# fc_shield.net
KiCad netlist of a schematic drawn in EAGLE
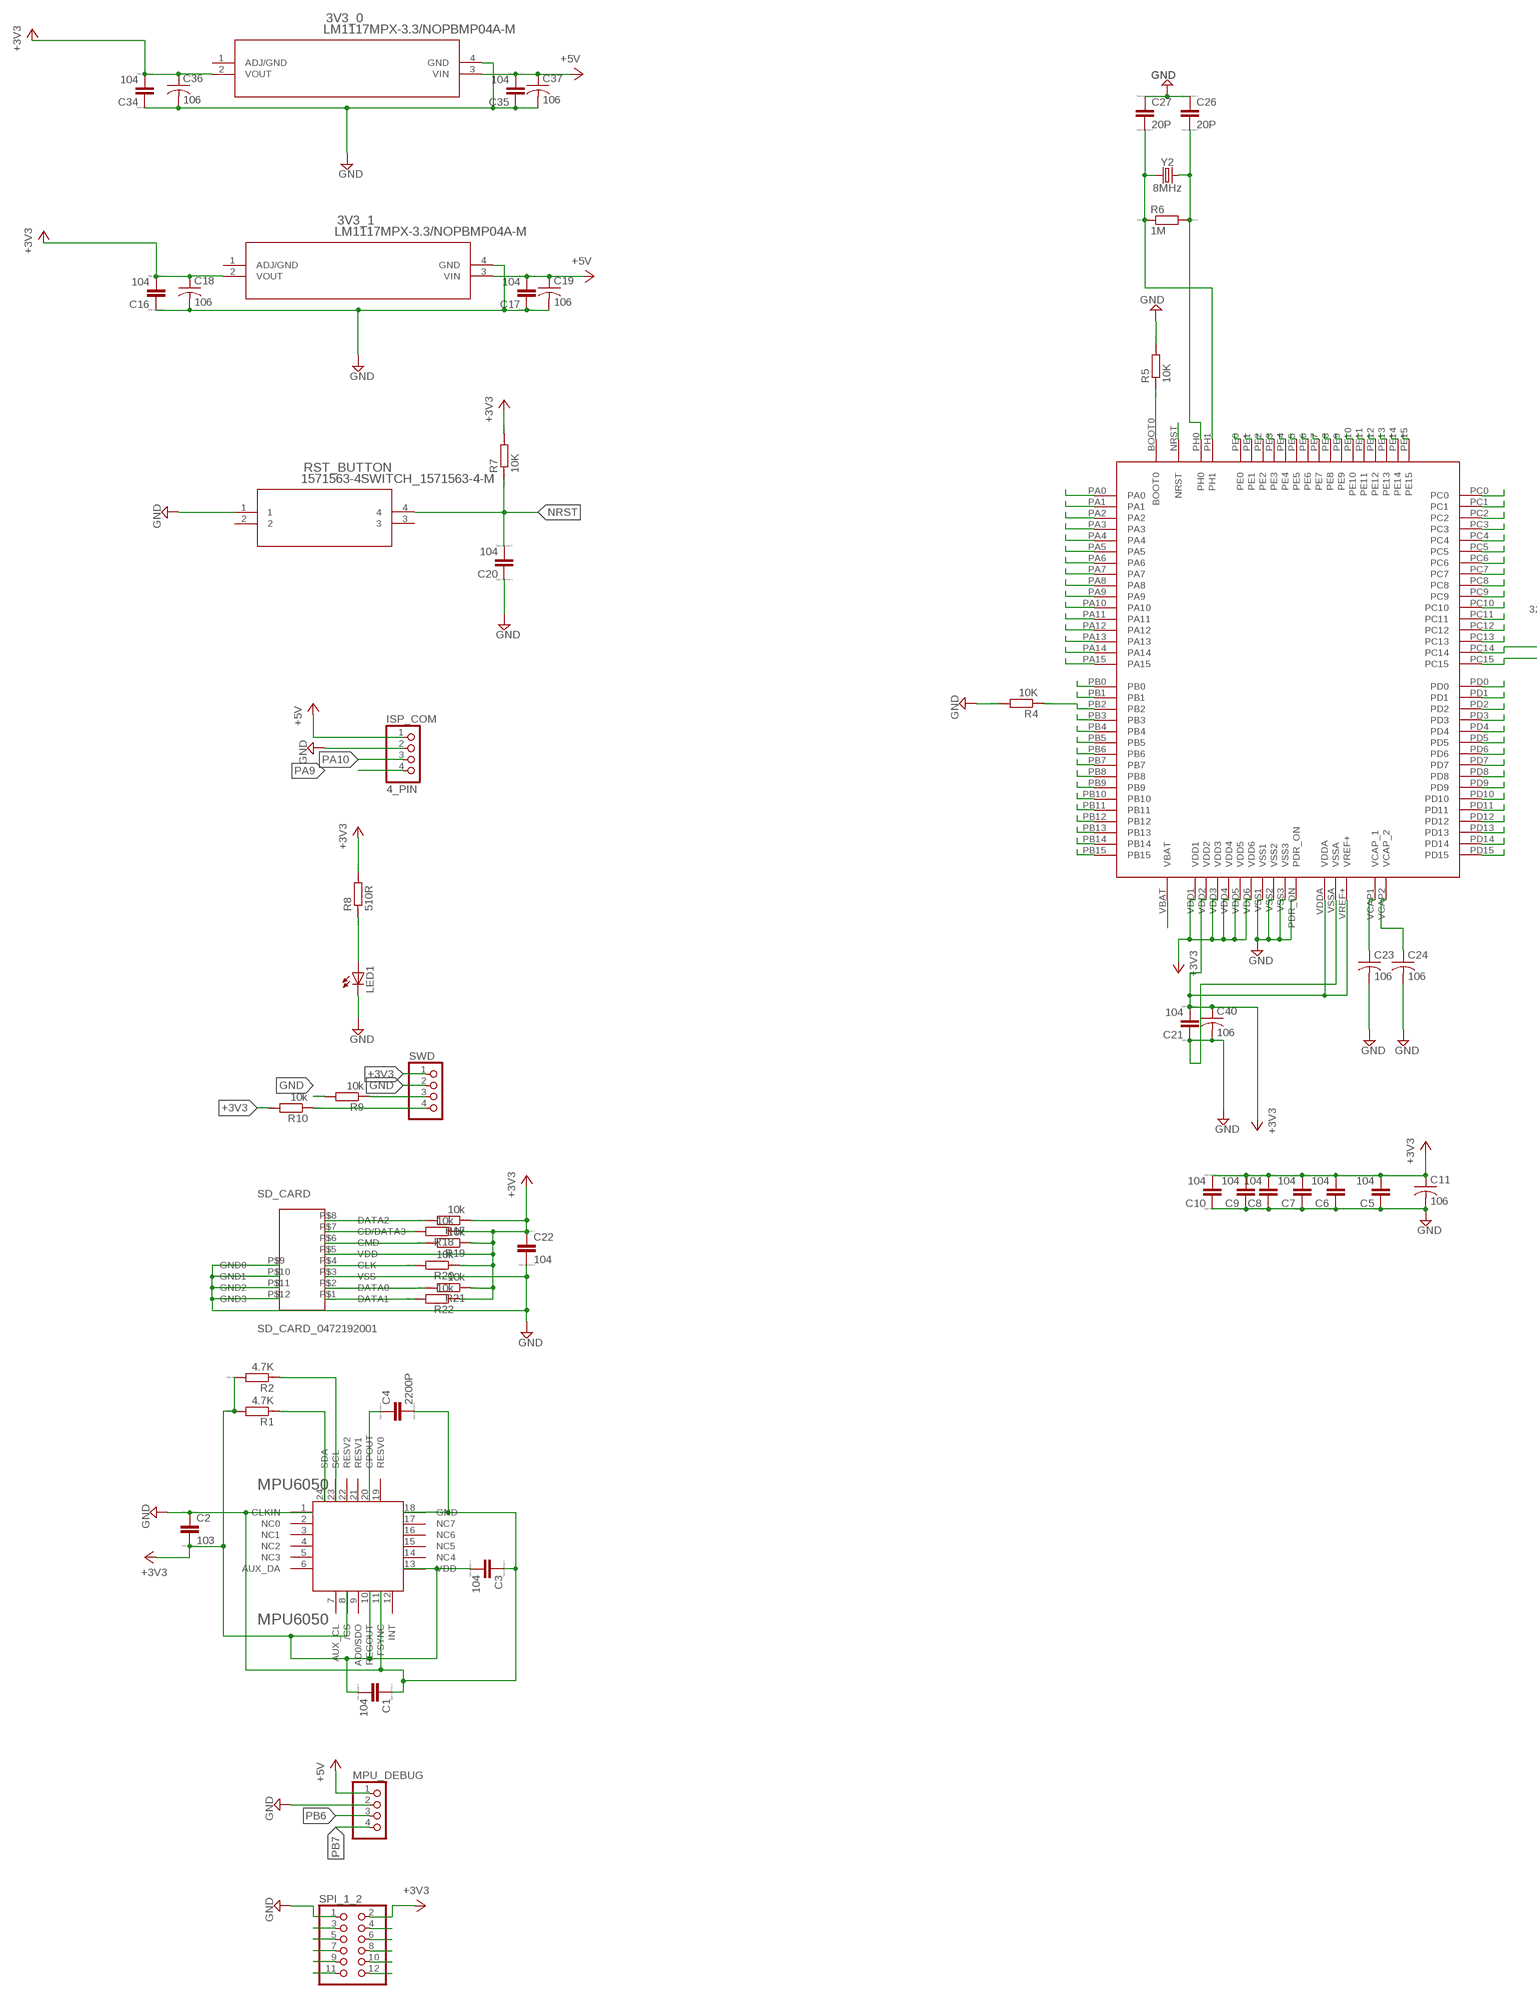
[diagram p0: schematic, sheet 1, part 1 of 2]
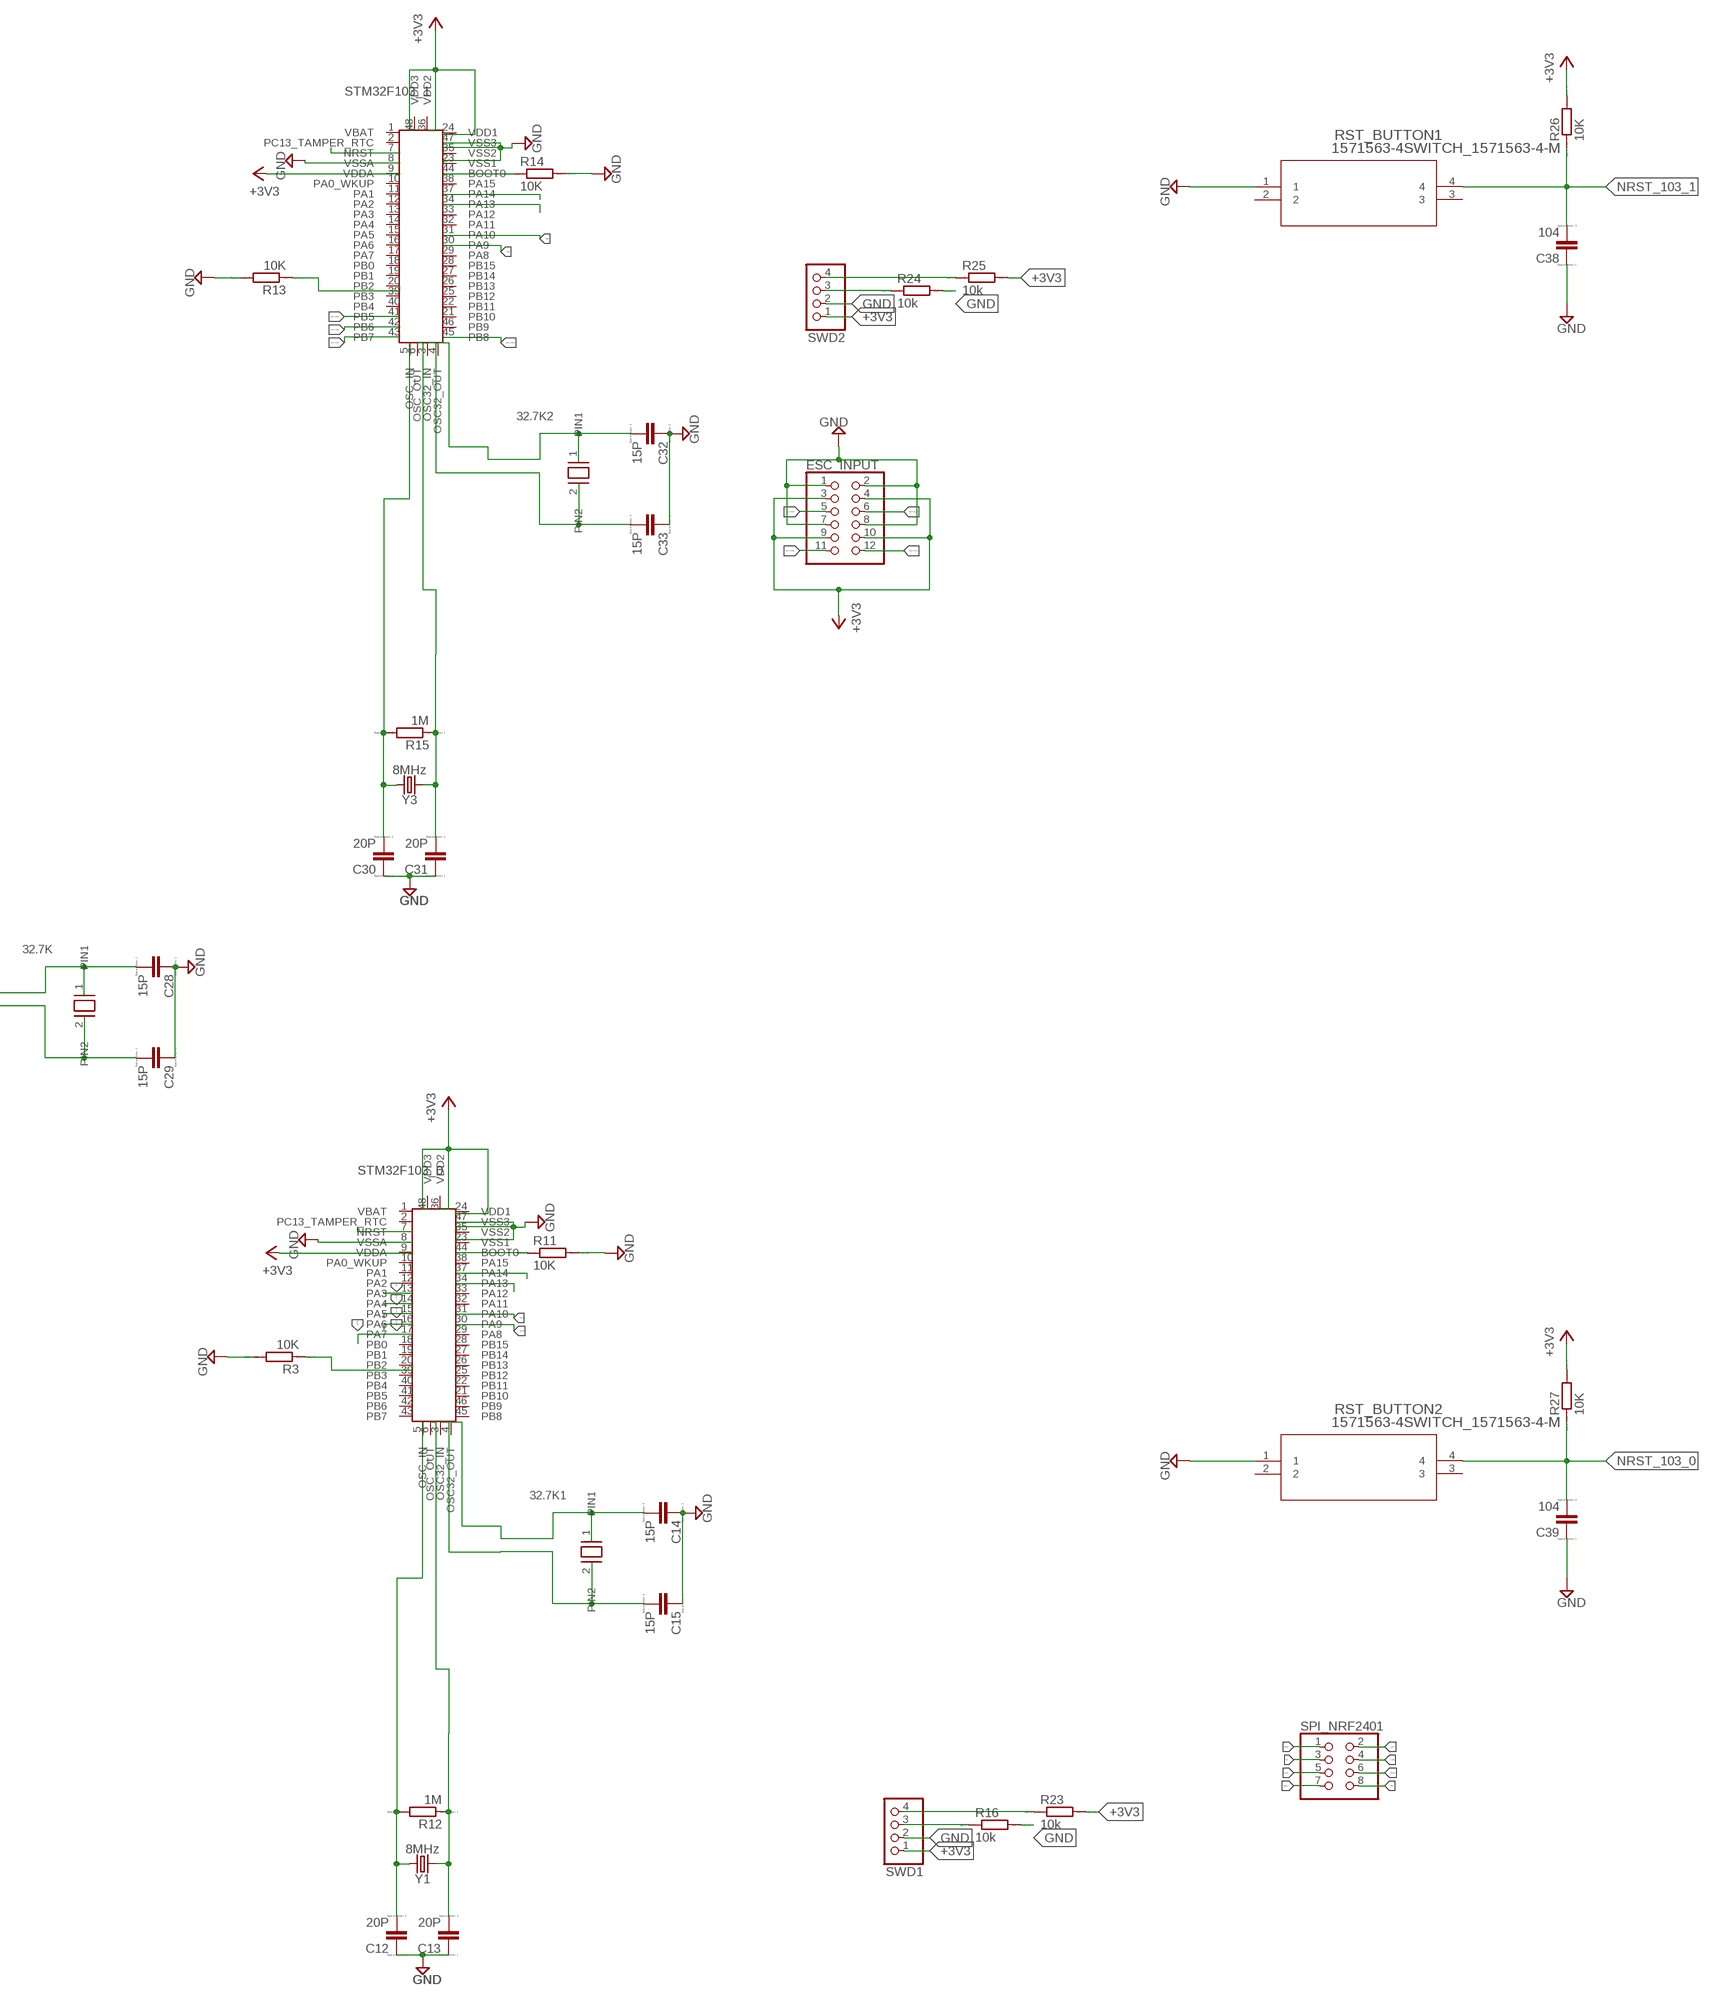
[diagram p1: schematic, sheet 1, part 2 of 2]

(export (version "E")
  (design (tool "Eeschema 10.0.6"))
  (components
    (comp (ref "3V3_0")
      (value "LM1117MPX-3.3/NOPBMP04A-M")
      (footprint "eagle-import:MP04A-M")
      (fields (field (name "MANUFACTURER_PART_NUMBER") "LM1117MPX3.3NOPB"))
      (libsource (lib "eagle-import") (part "LM1117MPX-3.3/NOPBMP04A-M"))
    )
    (comp (ref "3V3_1")
      (value "LM1117MPX-3.3/NOPBMP04A-M")
      (footprint "eagle-import:MP04A-M")
      (fields (field (name "MANUFACTURER_PART_NUMBER") "LM1117MPX3.3NOPB"))
      (libsource (lib "eagle-import") (part "LM1117MPX-3.3/NOPBMP04A-M"))
    )
    (comp (ref "32.7K")
      (value "CM315D")
      (footprint "eagle-import:CM315D_32.7K")
      (libsource (lib "eagle-import") (part "CM315D"))
    )
    (comp (ref "32.7K1")
      (value "CM315D")
      (footprint "eagle-import:CM315D_32.7K")
      (libsource (lib "eagle-import") (part "CM315D"))
    )
    (comp (ref "32.7K2")
      (value "CM315D")
      (footprint "eagle-import:CM315D_32.7K")
      (libsource (lib "eagle-import") (part "CM315D"))
    )
    (comp (ref "C1")
      (value "104")
      (footprint "eagle-import:C0603")
      (libsource (lib "eagle-import") (part "CC0603"))
    )
    (comp (ref "C2")
      (value "103")
      (footprint "eagle-import:C0603")
      (libsource (lib "eagle-import") (part "CC0603"))
    )
    (comp (ref "C3")
      (value "104")
      (footprint "eagle-import:C0603")
      (libsource (lib "eagle-import") (part "CC0603"))
    )
    (comp (ref "C4")
      (value "2200P")
      (footprint "eagle-import:C0603")
      (libsource (lib "eagle-import") (part "CC0603"))
    )
    (comp (ref "C5")
      (value "104")
      (footprint "eagle-import:C0603")
      (libsource (lib "eagle-import") (part "CC0603"))
    )
    (comp (ref "C6")
      (value "104")
      (footprint "eagle-import:C0603")
      (libsource (lib "eagle-import") (part "CC0603"))
    )
    (comp (ref "C7")
      (value "104")
      (footprint "eagle-import:C0603")
      (libsource (lib "eagle-import") (part "CC0603"))
    )
    (comp (ref "C8")
      (value "104")
      (footprint "eagle-import:C0603")
      (libsource (lib "eagle-import") (part "CC0603"))
    )
    (comp (ref "C9")
      (value "104")
      (footprint "eagle-import:C0603")
      (libsource (lib "eagle-import") (part "CC0603"))
    )
    (comp (ref "C10")
      (value "104")
      (footprint "eagle-import:C0603")
      (libsource (lib "eagle-import") (part "CC0603"))
    )
    (comp (ref "C11")
      (value "106")
      (footprint "eagle-import:C0805")
      (libsource (lib "eagle-import") (part "C-USC0805"))
    )
    (comp (ref "C12")
      (value "20P")
      (footprint "eagle-import:C0603")
      (libsource (lib "eagle-import") (part "CC0603"))
    )
    (comp (ref "C13")
      (value "20P")
      (footprint "eagle-import:C0603")
      (libsource (lib "eagle-import") (part "CC0603"))
    )
    (comp (ref "C14")
      (value "15P")
      (footprint "eagle-import:C0603")
      (libsource (lib "eagle-import") (part "CC0603"))
    )
    (comp (ref "C15")
      (value "15P")
      (footprint "eagle-import:C0603")
      (libsource (lib "eagle-import") (part "CC0603"))
    )
    (comp (ref "C16")
      (value "104")
      (footprint "eagle-import:C0603")
      (libsource (lib "eagle-import") (part "CC0603"))
    )
    (comp (ref "C17")
      (value "104")
      (footprint "eagle-import:C0603")
      (libsource (lib "eagle-import") (part "CC0603"))
    )
    (comp (ref "C18")
      (value "106")
      (footprint "eagle-import:C0805")
      (libsource (lib "eagle-import") (part "C-USC0805"))
    )
    (comp (ref "C19")
      (value "106")
      (footprint "eagle-import:C0805")
      (libsource (lib "eagle-import") (part "C-USC0805"))
    )
    (comp (ref "C20")
      (value "104")
      (footprint "eagle-import:C0603")
      (libsource (lib "eagle-import") (part "CC0603"))
    )
    (comp (ref "C21")
      (value "104")
      (footprint "eagle-import:C0603")
      (libsource (lib "eagle-import") (part "CC0603"))
    )
    (comp (ref "C22")
      (value "104")
      (footprint "eagle-import:C0603")
      (libsource (lib "eagle-import") (part "CC0603"))
    )
    (comp (ref "C23")
      (value "106")
      (footprint "eagle-import:C0805")
      (libsource (lib "eagle-import") (part "C-USC0805"))
    )
    (comp (ref "C24")
      (value "106")
      (footprint "eagle-import:C0805")
      (libsource (lib "eagle-import") (part "C-USC0805"))
    )
    (comp (ref "C26")
      (value "20P")
      (footprint "eagle-import:C0603")
      (libsource (lib "eagle-import") (part "CC0603"))
    )
    (comp (ref "C27")
      (value "20P")
      (footprint "eagle-import:C0603")
      (libsource (lib "eagle-import") (part "CC0603"))
    )
    (comp (ref "C28")
      (value "15P")
      (footprint "eagle-import:C0603")
      (libsource (lib "eagle-import") (part "CC0603"))
    )
    (comp (ref "C29")
      (value "15P")
      (footprint "eagle-import:C0603")
      (libsource (lib "eagle-import") (part "CC0603"))
    )
    (comp (ref "C30")
      (value "20P")
      (footprint "eagle-import:C0603")
      (libsource (lib "eagle-import") (part "CC0603"))
    )
    (comp (ref "C31")
      (value "20P")
      (footprint "eagle-import:C0603")
      (libsource (lib "eagle-import") (part "CC0603"))
    )
    (comp (ref "C32")
      (value "15P")
      (footprint "eagle-import:C0603")
      (libsource (lib "eagle-import") (part "CC0603"))
    )
    (comp (ref "C33")
      (value "15P")
      (footprint "eagle-import:C0603")
      (libsource (lib "eagle-import") (part "CC0603"))
    )
    (comp (ref "C34")
      (value "104")
      (footprint "eagle-import:C0603")
      (libsource (lib "eagle-import") (part "CC0603"))
    )
    (comp (ref "C35")
      (value "104")
      (footprint "eagle-import:C0603")
      (libsource (lib "eagle-import") (part "CC0603"))
    )
    (comp (ref "C36")
      (value "106")
      (footprint "eagle-import:C0805")
      (libsource (lib "eagle-import") (part "C-USC0805"))
    )
    (comp (ref "C37")
      (value "106")
      (footprint "eagle-import:C0805")
      (libsource (lib "eagle-import") (part "C-USC0805"))
    )
    (comp (ref "C38")
      (value "104")
      (footprint "eagle-import:C0603")
      (libsource (lib "eagle-import") (part "CC0603"))
    )
    (comp (ref "C39")
      (value "104")
      (footprint "eagle-import:C0603")
      (libsource (lib "eagle-import") (part "CC0603"))
    )
    (comp (ref "C40")
      (value "106")
      (footprint "eagle-import:C0805")
      (libsource (lib "eagle-import") (part "C-USC0805"))
    )
    (comp (ref "ESC_INPUT")
      (value "PINHD-2X6/90")
      (footprint "eagle-import:2X06_90")
      (libsource (lib "eagle-import") (part "PINHD-2X6/90"))
    )
    (comp (ref "ISP_COM")
      (value "4_PIN")
      (footprint "eagle-import:1X04")
      (libsource (lib "eagle-import") (part "PINHD-1X4"))
    )
    (comp (ref "LED1")
      (value "LEDCHIPLED_0805")
      (footprint "eagle-import:CHIPLED_0805")
      (libsource (lib "eagle-import") (part "LEDCHIPLED_0805"))
    )
    (comp (ref "MPU6050")
      (value "MPU6050")
      (footprint "eagle-import:MPU6050")
      (libsource (lib "eagle-import") (part "MPU6050"))
    )
    (comp (ref "MPU_DEBUG")
      (value "PINHD-1X4")
      (footprint "eagle-import:1X04")
      (libsource (lib "eagle-import") (part "PINHD-1X4"))
    )
    (comp (ref "R1")
      (value "4.7K")
      (footprint "eagle-import:R0603")
      (libsource (lib "eagle-import") (part "RR0603"))
    )
    (comp (ref "R2")
      (value "4.7K")
      (footprint "eagle-import:R0603")
      (libsource (lib "eagle-import") (part "RR0603"))
    )
    (comp (ref "R3")
      (value "10K")
      (footprint "eagle-import:R0603")
      (libsource (lib "eagle-import") (part "RR0603"))
    )
    (comp (ref "R4")
      (value "10K")
      (footprint "eagle-import:R0603")
      (libsource (lib "eagle-import") (part "RR0603"))
    )
    (comp (ref "R5")
      (value "10K")
      (footprint "eagle-import:R0603")
      (libsource (lib "eagle-import") (part "RR0603"))
    )
    (comp (ref "R6")
      (value "1M")
      (footprint "eagle-import:R0603")
      (libsource (lib "eagle-import") (part "RR0603"))
    )
    (comp (ref "R7")
      (value "10K")
      (footprint "eagle-import:R0603")
      (libsource (lib "eagle-import") (part "RR0603"))
    )
    (comp (ref "R8")
      (value "510R")
      (footprint "eagle-import:R0603")
      (libsource (lib "eagle-import") (part "RR0603"))
    )
    (comp (ref "R9")
      (value "10k")
      (footprint "eagle-import:R0603")
      (libsource (lib "eagle-import") (part "RR0603"))
    )
    (comp (ref "R10")
      (value "10k")
      (footprint "eagle-import:R0603")
      (libsource (lib "eagle-import") (part "RR0603"))
    )
    (comp (ref "R11")
      (value "10K")
      (footprint "eagle-import:R0603")
      (libsource (lib "eagle-import") (part "RR0603"))
    )
    (comp (ref "R12")
      (value "1M")
      (footprint "eagle-import:R0603")
      (libsource (lib "eagle-import") (part "RR0603"))
    )
    (comp (ref "R13")
      (value "10K")
      (footprint "eagle-import:R0603")
      (libsource (lib "eagle-import") (part "RR0603"))
    )
    (comp (ref "R14")
      (value "10K")
      (footprint "eagle-import:R0603")
      (libsource (lib "eagle-import") (part "RR0603"))
    )
    (comp (ref "R15")
      (value "1M")
      (footprint "eagle-import:R0603")
      (libsource (lib "eagle-import") (part "RR0603"))
    )
    (comp (ref "R16")
      (value "10k")
      (footprint "eagle-import:R0603")
      (libsource (lib "eagle-import") (part "RR0603"))
    )
    (comp (ref "R17")
      (value "10k")
      (footprint "eagle-import:R0603")
      (libsource (lib "eagle-import") (part "RR0603"))
    )
    (comp (ref "R18")
      (value "10k")
      (footprint "eagle-import:R0603")
      (libsource (lib "eagle-import") (part "RR0603"))
    )
    (comp (ref "R19")
      (value "10k")
      (footprint "eagle-import:R0603")
      (libsource (lib "eagle-import") (part "RR0603"))
    )
    (comp (ref "R20")
      (value "10k")
      (footprint "eagle-import:R0603")
      (libsource (lib "eagle-import") (part "RR0603"))
    )
    (comp (ref "R21")
      (value "10k")
      (footprint "eagle-import:R0603")
      (libsource (lib "eagle-import") (part "RR0603"))
    )
    (comp (ref "R22")
      (value "10k")
      (footprint "eagle-import:R0603")
      (libsource (lib "eagle-import") (part "RR0603"))
    )
    (comp (ref "R23")
      (value "10k")
      (footprint "eagle-import:R0603")
      (libsource (lib "eagle-import") (part "RR0603"))
    )
    (comp (ref "R24")
      (value "10k")
      (footprint "eagle-import:R0603")
      (libsource (lib "eagle-import") (part "RR0603"))
    )
    (comp (ref "R25")
      (value "10k")
      (footprint "eagle-import:R0603")
      (libsource (lib "eagle-import") (part "RR0603"))
    )
    (comp (ref "R26")
      (value "10K")
      (footprint "eagle-import:R0603")
      (libsource (lib "eagle-import") (part "RR0603"))
    )
    (comp (ref "R27")
      (value "10K")
      (footprint "eagle-import:R0603")
      (libsource (lib "eagle-import") (part "RR0603"))
    )
    (comp (ref "RST_BUTTON")
      (value "1571563-4SWITCH_1571563-4-M")
      (footprint "eagle-import:SWITCH_1571563-4-M")
      (fields (field (name "MANUFACTURER_PART_NUMBER") "15715634"))
      (libsource (lib "eagle-import") (part "1571563-4SWITCH_1571563-4-M"))
    )
    (comp (ref "RST_BUTTON1")
      (value "1571563-4SWITCH_1571563-4-M")
      (footprint "eagle-import:SWITCH_1571563-4-M")
      (fields (field (name "MANUFACTURER_PART_NUMBER") "15715634"))
      (libsource (lib "eagle-import") (part "1571563-4SWITCH_1571563-4-M"))
    )
    (comp (ref "RST_BUTTON2")
      (value "1571563-4SWITCH_1571563-4-M")
      (footprint "eagle-import:SWITCH_1571563-4-M")
      (fields (field (name "MANUFACTURER_PART_NUMBER") "15715634"))
      (libsource (lib "eagle-import") (part "1571563-4SWITCH_1571563-4-M"))
    )
    (comp (ref "SD_CARD")
      (value "SD_CARD_0472192001")
      (footprint "eagle-import:0472192001")
      (libsource (lib "eagle-import") (part "SD_CARD_0472192001"))
    )
    (comp (ref "SPI_1_2")
      (value "PINHD-2X6/90")
      (footprint "eagle-import:2X06_90")
      (libsource (lib "eagle-import") (part "PINHD-2X6/90"))
    )
    (comp (ref "SPI_NRF2401")
      (value "PINHD-2X4")
      (footprint "eagle-import:2X04")
      (libsource (lib "eagle-import") (part "PINHD-2X4"))
    )
    (comp (ref "STM32F103_0")
      (value "STM32F103C8T6")
      (footprint "eagle-import:STM32103C8T6_LQFP48")
      (libsource (lib "eagle-import") (part "STM32F103C8T6"))
    )
    (comp (ref "STM32F103_1")
      (value "STM32F103C8T6")
      (footprint "eagle-import:STM32103C8T6_LQFP48")
      (libsource (lib "eagle-import") (part "STM32F103C8T6"))
    )
    (comp (ref "SWD")
      (value "PINHD-1X4")
      (footprint "eagle-import:1X04")
      (libsource (lib "eagle-import") (part "PINHD-1X4"))
    )
    (comp (ref "SWD1")
      (value "PINHD-1X4")
      (footprint "eagle-import:1X04")
      (libsource (lib "eagle-import") (part "PINHD-1X4"))
    )
    (comp (ref "SWD2")
      (value "PINHD-1X4")
      (footprint "eagle-import:1X04")
      (libsource (lib "eagle-import") (part "PINHD-1X4"))
    )
    (comp (ref "U$1")
      (value "STM32F4V_100PIN_GENERIC")
      (footprint "eagle-import:LQFP100")
      (libsource (lib "eagle-import") (part "STM32F4V_100PIN_GENERIC"))
    )
    (comp (ref "Y1")
      (value "8MHz")
      (footprint "eagle-import:HC49UP")
      (libsource (lib "eagle-import") (part "CRYSTAL-8MHZSMD-HC49UP"))
    )
    (comp (ref "Y2")
      (value "8MHz")
      (footprint "eagle-import:HC49UP")
      (libsource (lib "eagle-import") (part "CRYSTAL-8MHZSMD-HC49UP"))
    )
    (comp (ref "Y3")
      (value "8MHz")
      (footprint "eagle-import:HC49UP")
      (libsource (lib "eagle-import") (part "CRYSTAL-8MHZSMD-HC49UP"))
    )
  )
  (nets
    (net (code "1") (name "+3V3") (class "Default")
      (node (ref "3V3_0") (pin "2") (pinfunction "VOUT_2") (pintype "passive"))
      (node (ref "3V3_1") (pin "2") (pinfunction "VOUT_2") (pintype "passive"))
      (node (ref "C1") (pin "2") (pinfunction "2_2") (pintype "passive"))
      (node (ref "C10") (pin "2") (pinfunction "2_2") (pintype "passive"))
      (node (ref "C11") (pin "1") (pinfunction "1_1") (pintype "passive"))
      (node (ref "C16") (pin "2") (pinfunction "2_2") (pintype "passive"))
      (node (ref "C18") (pin "1") (pinfunction "1_1") (pintype "passive"))
      (node (ref "C2") (pin "2") (pinfunction "2_2") (pintype "passive"))
      (node (ref "C21") (pin "2") (pinfunction "2_2") (pintype "passive"))
      (node (ref "C22") (pin "1") (pinfunction "1_1") (pintype "passive"))
      (node (ref "C3") (pin "2") (pinfunction "2_2") (pintype "passive"))
      (node (ref "C34") (pin "2") (pinfunction "2_2") (pintype "passive"))
      (node (ref "C36") (pin "1") (pinfunction "1_1") (pintype "passive"))
      (node (ref "C40") (pin "1") (pinfunction "1_1") (pintype "passive"))
      (node (ref "C5") (pin "2") (pinfunction "2_2") (pintype "passive"))
      (node (ref "C6") (pin "2") (pinfunction "2_2") (pintype "passive"))
      (node (ref "C7") (pin "2") (pinfunction "2_2") (pintype "passive"))
      (node (ref "C8") (pin "2") (pinfunction "2_2") (pintype "passive"))
      (node (ref "C9") (pin "2") (pinfunction "2_2") (pintype "passive"))
      (node (ref "ESC_INPUT") (pin "10") (pinfunction "10_10") (pintype "passive"))
      (node (ref "ESC_INPUT") (pin "3") (pinfunction "3_3") (pintype "passive"))
      (node (ref "ESC_INPUT") (pin "4") (pinfunction "4_4") (pintype "passive"))
      (node (ref "ESC_INPUT") (pin "9") (pinfunction "9_9") (pintype "passive"))
      (node (ref "MPU6050") (pin "10") (pinfunction "REGOUT_10") (pintype "bidirectional"))
      (node (ref "MPU6050") (pin "13") (pinfunction "VDD_13") (pintype "bidirectional"))
      (node (ref "MPU6050") (pin "8") (pinfunction "/CS_8") (pintype "bidirectional"))
      (node (ref "R1") (pin "2") (pinfunction "2_2") (pintype "passive"))
      (node (ref "R10") (pin "2") (pinfunction "2_2") (pintype "passive"))
      (node (ref "R17") (pin "1") (pinfunction "1_1") (pintype "passive"))
      (node (ref "R18") (pin "1") (pinfunction "1_1") (pintype "passive"))
      (node (ref "R19") (pin "1") (pinfunction "1_1") (pintype "passive"))
      (node (ref "R2") (pin "2") (pinfunction "2_2") (pintype "passive"))
      (node (ref "R20") (pin "1") (pinfunction "1_1") (pintype "passive"))
      (node (ref "R21") (pin "1") (pinfunction "1_1") (pintype "passive"))
      (node (ref "R22") (pin "1") (pinfunction "1_1") (pintype "passive"))
      (node (ref "R23") (pin "2") (pinfunction "2_2") (pintype "passive"))
      (node (ref "R25") (pin "2") (pinfunction "2_2") (pintype "passive"))
      (node (ref "R26") (pin "2") (pinfunction "2_2") (pintype "passive"))
      (node (ref "R27") (pin "2") (pinfunction "2_2") (pintype "passive"))
      (node (ref "R7") (pin "2") (pinfunction "2_2") (pintype "passive"))
      (node (ref "R8") (pin "2") (pinfunction "2_2") (pintype "passive"))
      (node (ref "SD_CARD") (pin "P$5") (pinfunction "VDD_P$5") (pintype "bidirectional"))
      (node (ref "SPI_1_2") (pin "2") (pinfunction "2_2") (pintype "passive"))
      (node (ref "SPI_NRF2401") (pin "2") (pinfunction "2_2") (pintype "passive"))
      (node (ref "STM32F103_0") (pin "24") (pinfunction "VDD1_24") (pintype "bidirectional"))
      (node (ref "STM32F103_0") (pin "36") (pinfunction "VDD2_36") (pintype "bidirectional"))
      (node (ref "STM32F103_0") (pin "48") (pinfunction "VDD3_48") (pintype "bidirectional"))
      (node (ref "STM32F103_0") (pin "9") (pinfunction "VDDA_9") (pintype "bidirectional"))
      (node (ref "STM32F103_1") (pin "24") (pinfunction "VDD1_24") (pintype "bidirectional"))
      (node (ref "STM32F103_1") (pin "36") (pinfunction "VDD2_36") (pintype "bidirectional"))
      (node (ref "STM32F103_1") (pin "48") (pinfunction "VDD3_48") (pintype "bidirectional"))
      (node (ref "STM32F103_1") (pin "9") (pinfunction "VDDA_9") (pintype "bidirectional"))
      (node (ref "SWD") (pin "1") (pinfunction "1_1") (pintype "passive"))
      (node (ref "SWD1") (pin "1") (pinfunction "1_1") (pintype "passive"))
      (node (ref "SWD2") (pin "1") (pinfunction "1_1") (pintype "passive"))
      (node (ref "U$1") (pin "VDD1") (pinfunction "VDD1_VDD1") (pintype "bidirectional"))
      (node (ref "U$1") (pin "VDD2") (pinfunction "VDD2_VDD2") (pintype "bidirectional"))
      (node (ref "U$1") (pin "VDD3") (pinfunction "VDD3_VDD3") (pintype "bidirectional"))
      (node (ref "U$1") (pin "VDD4") (pinfunction "VDD4_VDD4") (pintype "bidirectional"))
      (node (ref "U$1") (pin "VDD5") (pinfunction "VDD5_VDD5") (pintype "bidirectional"))
      (node (ref "U$1") (pin "VDD6") (pinfunction "VDD6_VDD6") (pintype "bidirectional"))
      (node (ref "U$1") (pin "VDDA") (pinfunction "VDDA_VDDA") (pintype "bidirectional"))
      (node (ref "U$1") (pin "VREF+") (pinfunction "VREF+_VREF+") (pintype "bidirectional"))
    )
    (net (code "2") (name "+5V") (class "Default")
      (node (ref "3V3_0") (pin "3") (pinfunction "VIN_3") (pintype "input"))
      (node (ref "3V3_1") (pin "3") (pinfunction "VIN_3") (pintype "input"))
      (node (ref "C17") (pin "2") (pinfunction "2_2") (pintype "passive"))
      (node (ref "C19") (pin "1") (pinfunction "1_1") (pintype "passive"))
      (node (ref "C35") (pin "2") (pinfunction "2_2") (pintype "passive"))
      (node (ref "C37") (pin "1") (pinfunction "1_1") (pintype "passive"))
      (node (ref "ISP_COM") (pin "1") (pinfunction "1_1") (pintype "passive"))
      (node (ref "MPU_DEBUG") (pin "1") (pinfunction "1_1") (pintype "passive"))
    )
    (net (code "3") (name "/PA5") (class "Default")
      (node (ref "SPI_1_2") (pin "7") (pinfunction "7_7") (pintype "passive"))
      (node (ref "U$1") (pin "PA5") (pinfunction "PA5_PA5") (pintype "bidirectional"))
    )
    (net (code "4") (name "/PA6") (class "Default")
      (node (ref "SPI_1_2") (pin "9") (pinfunction "9_9") (pintype "passive"))
      (node (ref "U$1") (pin "PA6") (pinfunction "PA6_PA6") (pintype "bidirectional"))
    )
    (net (code "5") (name "/PA7") (class "Default")
      (node (ref "SPI_1_2") (pin "11") (pinfunction "11_11") (pintype "passive"))
      (node (ref "U$1") (pin "PA7") (pinfunction "PA7_PA7") (pintype "bidirectional"))
    )
    (net (code "6") (name "/PA13") (class "Default")
      (node (ref "R10") (pin "1") (pinfunction "1_1") (pintype "passive"))
      (node (ref "SWD") (pin "4") (pinfunction "4_4") (pintype "passive"))
      (node (ref "U$1") (pin "PA13") (pinfunction "PA13_PA13") (pintype "bidirectional"))
    )
    (net (code "7") (name "/PA14") (class "Default")
      (node (ref "R9") (pin "1") (pinfunction "1_1") (pintype "passive"))
      (node (ref "SWD") (pin "3") (pinfunction "3_3") (pintype "passive"))
      (node (ref "U$1") (pin "PA14") (pinfunction "PA14_PA14") (pintype "bidirectional"))
    )
    (net (code "8") (name "/PB10") (class "Default")
      (node (ref "SPI_1_2") (pin "8") (pinfunction "8_8") (pintype "passive"))
      (node (ref "U$1") (pin "PB10") (pinfunction "PB10_PB10") (pintype "bidirectional"))
    )
    (net (code "9") (name "/PC2") (class "Default")
      (node (ref "SPI_1_2") (pin "10") (pinfunction "10_10") (pintype "passive"))
      (node (ref "U$1") (pin "PC2") (pinfunction "PC2_PC2") (pintype "bidirectional"))
    )
    (net (code "10") (name "/PC3") (class "Default")
      (node (ref "SPI_1_2") (pin "12") (pinfunction "12_12") (pintype "passive"))
      (node (ref "U$1") (pin "PC3") (pinfunction "PC3_PC3") (pintype "bidirectional"))
    )
    (net (code "11") (name "/PC4") (class "Default")
      (node (ref "SPI_1_2") (pin "3") (pinfunction "3_3") (pintype "passive"))
      (node (ref "U$1") (pin "PC4") (pinfunction "PC4_PC4") (pintype "bidirectional"))
    )
    (net (code "12") (name "/PC5") (class "Default")
      (node (ref "SPI_1_2") (pin "5") (pinfunction "5_5") (pintype "passive"))
      (node (ref "U$1") (pin "PC5") (pinfunction "PC5_PC5") (pintype "bidirectional"))
    )
    (net (code "13") (name "/PC8") (class "Default")
      (node (ref "R21") (pin "2") (pinfunction "2_2") (pintype "passive"))
      (node (ref "SD_CARD") (pin "P$2") (pinfunction "DATA0_P$2") (pintype "bidirectional"))
      (node (ref "U$1") (pin "PC8") (pinfunction "PC8_PC8") (pintype "bidirectional"))
    )
    (net (code "14") (name "/PC9") (class "Default")
      (node (ref "R22") (pin "2") (pinfunction "2_2") (pintype "passive"))
      (node (ref "SD_CARD") (pin "P$1") (pinfunction "DATA1_P$1") (pintype "bidirectional"))
      (node (ref "U$1") (pin "PC9") (pinfunction "PC9_PC9") (pintype "bidirectional"))
    )
    (net (code "15") (name "/PC10") (class "Default")
      (node (ref "R17") (pin "2") (pinfunction "2_2") (pintype "passive"))
      (node (ref "SD_CARD") (pin "P$8") (pinfunction "DATA2_P$8") (pintype "bidirectional"))
      (node (ref "U$1") (pin "PC10") (pinfunction "PC10_PC10") (pintype "bidirectional"))
    )
    (net (code "16") (name "/PC11") (class "Default")
      (node (ref "R18") (pin "2") (pinfunction "2_2") (pintype "passive"))
      (node (ref "SD_CARD") (pin "P$7") (pinfunction "CD/DATA3_P$7") (pintype "bidirectional"))
      (node (ref "U$1") (pin "PC11") (pinfunction "PC11_PC11") (pintype "bidirectional"))
    )
    (net (code "17") (name "/PC12") (class "Default")
      (node (ref "R20") (pin "2") (pinfunction "2_2") (pintype "passive"))
      (node (ref "SD_CARD") (pin "P$4") (pinfunction "CLK_P$4") (pintype "bidirectional"))
      (node (ref "U$1") (pin "PC12") (pinfunction "PC12_PC12") (pintype "bidirectional"))
    )
    (net (code "18") (name "/PD2") (class "Default")
      (node (ref "R19") (pin "2") (pinfunction "2_2") (pintype "passive"))
      (node (ref "SD_CARD") (pin "P$6") (pinfunction "CMD_P$6") (pintype "bidirectional"))
      (node (ref "U$1") (pin "PD2") (pinfunction "PD2_PD2") (pintype "bidirectional"))
    )
    (net (code "19") (name "/PE7") (class "Default")
      (node (ref "SPI_1_2") (pin "4") (pinfunction "4_4") (pintype "passive"))
      (node (ref "U$1") (pin "PE7") (pinfunction "PE7_PE7") (pintype "bidirectional"))
    )
    (net (code "20") (name "/PE8") (class "Default")
      (node (ref "SPI_1_2") (pin "6") (pinfunction "6_6") (pintype "passive"))
      (node (ref "U$1") (pin "PE8") (pinfunction "PE8_PE8") (pintype "bidirectional"))
    )
    (net (code "21") (name "/SWCLK_103_0") (class "Default")
      (node (ref "R16") (pin "1") (pinfunction "1_1") (pintype "passive"))
      (node (ref "STM32F103_0") (pin "37") (pinfunction "PA14_37") (pintype "bidirectional"))
      (node (ref "SWD1") (pin "3") (pinfunction "3_3") (pintype "passive"))
    )
    (net (code "22") (name "/SWCLK_103_1") (class "Default")
      (node (ref "R24") (pin "1") (pinfunction "1_1") (pintype "passive"))
      (node (ref "STM32F103_1") (pin "37") (pinfunction "PA14_37") (pintype "bidirectional"))
      (node (ref "SWD2") (pin "3") (pinfunction "3_3") (pintype "passive"))
    )
    (net (code "23") (name "/SWDIO_103_0") (class "Default")
      (node (ref "R23") (pin "1") (pinfunction "1_1") (pintype "passive"))
      (node (ref "STM32F103_0") (pin "34") (pinfunction "PA13_34") (pintype "bidirectional"))
      (node (ref "SWD1") (pin "4") (pinfunction "4_4") (pintype "passive"))
    )
    (net (code "24") (name "/SWDIO_103_1") (class "Default")
      (node (ref "R25") (pin "1") (pinfunction "1_1") (pintype "passive"))
      (node (ref "STM32F103_1") (pin "34") (pinfunction "PA13_34") (pintype "bidirectional"))
      (node (ref "SWD2") (pin "4") (pinfunction "4_4") (pintype "passive"))
    )
    (net (code "25") (name "CE") (class "Default")
      (node (ref "SPI_NRF2401") (pin "3") (pinfunction "3_3") (pintype "passive"))
      (node (ref "STM32F103_0") (pin "13") (pinfunction "PA3_13") (pintype "bidirectional"))
    )
    (net (code "26") (name "CSN") (class "Default")
      (node (ref "SPI_NRF2401") (pin "4") (pinfunction "4_4") (pintype "passive"))
      (node (ref "STM32F103_0") (pin "14") (pinfunction "PA4_14") (pintype "bidirectional"))
    )
    (net (code "27") (name "GND") (class "Default")
      (node (ref "3V3_0") (pin "4") (pinfunction "GND_4") (pintype "power_in"))
      (node (ref "3V3_1") (pin "4") (pinfunction "GND_4") (pintype "power_in"))
      (node (ref "C1") (pin "1") (pinfunction "1_1") (pintype "passive"))
      (node (ref "C10") (pin "1") (pinfunction "1_1") (pintype "passive"))
      (node (ref "C11") (pin "2") (pinfunction "2_2") (pintype "passive"))
      (node (ref "C12") (pin "1") (pinfunction "1_1") (pintype "passive"))
      (node (ref "C13") (pin "1") (pinfunction "1_1") (pintype "passive"))
      (node (ref "C14") (pin "1") (pinfunction "1_1") (pintype "passive"))
      (node (ref "C15") (pin "1") (pinfunction "1_1") (pintype "passive"))
      (node (ref "C16") (pin "1") (pinfunction "1_1") (pintype "passive"))
      (node (ref "C17") (pin "1") (pinfunction "1_1") (pintype "passive"))
      (node (ref "C18") (pin "2") (pinfunction "2_2") (pintype "passive"))
      (node (ref "C19") (pin "2") (pinfunction "2_2") (pintype "passive"))
      (node (ref "C2") (pin "1") (pinfunction "1_1") (pintype "passive"))
      (node (ref "C20") (pin "1") (pinfunction "1_1") (pintype "passive"))
      (node (ref "C21") (pin "1") (pinfunction "1_1") (pintype "passive"))
      (node (ref "C22") (pin "2") (pinfunction "2_2") (pintype "passive"))
      (node (ref "C23") (pin "2") (pinfunction "2_2") (pintype "passive"))
      (node (ref "C24") (pin "2") (pinfunction "2_2") (pintype "passive"))
      (node (ref "C26") (pin "1") (pinfunction "1_1") (pintype "passive"))
      (node (ref "C27") (pin "1") (pinfunction "1_1") (pintype "passive"))
      (node (ref "C28") (pin "1") (pinfunction "1_1") (pintype "passive"))
      (node (ref "C29") (pin "1") (pinfunction "1_1") (pintype "passive"))
      (node (ref "C3") (pin "1") (pinfunction "1_1") (pintype "passive"))
      (node (ref "C30") (pin "1") (pinfunction "1_1") (pintype "passive"))
      (node (ref "C31") (pin "1") (pinfunction "1_1") (pintype "passive"))
      (node (ref "C32") (pin "1") (pinfunction "1_1") (pintype "passive"))
      (node (ref "C33") (pin "1") (pinfunction "1_1") (pintype "passive"))
      (node (ref "C34") (pin "1") (pinfunction "1_1") (pintype "passive"))
      (node (ref "C35") (pin "1") (pinfunction "1_1") (pintype "passive"))
      (node (ref "C36") (pin "2") (pinfunction "2_2") (pintype "passive"))
      (node (ref "C37") (pin "2") (pinfunction "2_2") (pintype "passive"))
      (node (ref "C38") (pin "1") (pinfunction "1_1") (pintype "passive"))
      (node (ref "C39") (pin "1") (pinfunction "1_1") (pintype "passive"))
      (node (ref "C4") (pin "2") (pinfunction "2_2") (pintype "passive"))
      (node (ref "C40") (pin "2") (pinfunction "2_2") (pintype "passive"))
      (node (ref "C5") (pin "1") (pinfunction "1_1") (pintype "passive"))
      (node (ref "C6") (pin "1") (pinfunction "1_1") (pintype "passive"))
      (node (ref "C7") (pin "1") (pinfunction "1_1") (pintype "passive"))
      (node (ref "C8") (pin "1") (pinfunction "1_1") (pintype "passive"))
      (node (ref "C9") (pin "1") (pinfunction "1_1") (pintype "passive"))
      (node (ref "ESC_INPUT") (pin "1") (pinfunction "1_1") (pintype "passive"))
      (node (ref "ESC_INPUT") (pin "2") (pinfunction "2_2") (pintype "passive"))
      (node (ref "ESC_INPUT") (pin "7") (pinfunction "7_7") (pintype "passive"))
      (node (ref "ESC_INPUT") (pin "8") (pinfunction "8_8") (pintype "passive"))
      (node (ref "ISP_COM") (pin "2") (pinfunction "2_2") (pintype "passive"))
      (node (ref "LED1") (pin "C") (pinfunction "C_C") (pintype "passive"))
      (node (ref "MPU6050") (pin "1") (pinfunction "CLKIN_1") (pintype "bidirectional"))
      (node (ref "MPU6050") (pin "11") (pinfunction "FSYNC_11") (pintype "bidirectional"))
      (node (ref "MPU6050") (pin "18") (pinfunction "GND_18") (pintype "bidirectional"))
      (node (ref "MPU_DEBUG") (pin "2") (pinfunction "2_2") (pintype "passive"))
      (node (ref "R11") (pin "2") (pinfunction "2_2") (pintype "passive"))
      (node (ref "R13") (pin "2") (pinfunction "2_2") (pintype "passive"))
      (node (ref "R14") (pin "2") (pinfunction "2_2") (pintype "passive"))
      (node (ref "R16") (pin "2") (pinfunction "2_2") (pintype "passive"))
      (node (ref "R24") (pin "2") (pinfunction "2_2") (pintype "passive"))
      (node (ref "R3") (pin "2") (pinfunction "2_2") (pintype "passive"))
      (node (ref "R4") (pin "2") (pinfunction "2_2") (pintype "passive"))
      (node (ref "R5") (pin "2") (pinfunction "2_2") (pintype "passive"))
      (node (ref "R9") (pin "2") (pinfunction "2_2") (pintype "passive"))
      (node (ref "RST_BUTTON") (pin "1") (pinfunction "1_1") (pintype "passive"))
      (node (ref "RST_BUTTON1") (pin "1") (pinfunction "1_1") (pintype "passive"))
      (node (ref "RST_BUTTON2") (pin "1") (pinfunction "1_1") (pintype "passive"))
      (node (ref "SD_CARD") (pin "P$10") (pinfunction "GND1_P$10") (pintype "bidirectional"))
      (node (ref "SD_CARD") (pin "P$11") (pinfunction "GND2_P$11") (pintype "bidirectional"))
      (node (ref "SD_CARD") (pin "P$12") (pinfunction "GND3_P$12") (pintype "bidirectional"))
      (node (ref "SD_CARD") (pin "P$3") (pinfunction "VSS_P$3") (pintype "bidirectional"))
      (node (ref "SD_CARD") (pin "P$9") (pinfunction "GND0_P$9") (pintype "bidirectional"))
      (node (ref "SPI_1_2") (pin "1") (pinfunction "1_1") (pintype "passive"))
      (node (ref "SPI_NRF2401") (pin "1") (pinfunction "1_1") (pintype "passive"))
      (node (ref "STM32F103_0") (pin "23") (pinfunction "VSS1_23") (pintype "bidirectional"))
      (node (ref "STM32F103_0") (pin "35") (pinfunction "VSS2_35") (pintype "bidirectional"))
      (node (ref "STM32F103_0") (pin "47") (pinfunction "VSS3_47") (pintype "bidirectional"))
      (node (ref "STM32F103_0") (pin "8") (pinfunction "VSSA_8") (pintype "bidirectional"))
      (node (ref "STM32F103_1") (pin "23") (pinfunction "VSS1_23") (pintype "bidirectional"))
      (node (ref "STM32F103_1") (pin "35") (pinfunction "VSS2_35") (pintype "bidirectional"))
      (node (ref "STM32F103_1") (pin "47") (pinfunction "VSS3_47") (pintype "bidirectional"))
      (node (ref "STM32F103_1") (pin "8") (pinfunction "VSSA_8") (pintype "bidirectional"))
      (node (ref "SWD") (pin "2") (pinfunction "2_2") (pintype "passive"))
      (node (ref "SWD1") (pin "2") (pinfunction "2_2") (pintype "passive"))
      (node (ref "SWD2") (pin "2") (pinfunction "2_2") (pintype "passive"))
      (node (ref "U$1") (pin "PDR_ON") (pinfunction "PDR_ON_PDR_ON") (pintype "bidirectional"))
      (node (ref "U$1") (pin "VSS1") (pinfunction "VSS1_VSS1") (pintype "bidirectional"))
      (node (ref "U$1") (pin "VSS2") (pinfunction "VSS2_VSS2") (pintype "bidirectional"))
      (node (ref "U$1") (pin "VSS3") (pinfunction "VSS3_VSS3") (pintype "bidirectional"))
      (node (ref "U$1") (pin "VSSA") (pinfunction "VSSA_VSSA") (pintype "bidirectional"))
    )
    (net (code "28") (name "IRQ") (class "Default")
      (node (ref "SPI_NRF2401") (pin "8") (pinfunction "8_8") (pintype "passive"))
    )
    (net (code "29") (name "MISO") (class "Default")
      (node (ref "SPI_NRF2401") (pin "7") (pinfunction "7_7") (pintype "passive"))
      (node (ref "STM32F103_0") (pin "16") (pinfunction "PA6_16") (pintype "bidirectional"))
    )
    (net (code "30") (name "MOSI") (class "Default")
      (node (ref "SPI_NRF2401") (pin "6") (pinfunction "6_6") (pintype "passive"))
      (node (ref "STM32F103_0") (pin "17") (pinfunction "PA7_17") (pintype "bidirectional"))
    )
    (net (code "31") (name "MOTOR1") (class "Default")
      (node (ref "ESC_INPUT") (pin "5") (pinfunction "5_5") (pintype "passive"))
      (node (ref "STM32F103_1") (pin "41") (pinfunction "PB5_41") (pintype "bidirectional"))
    )
    (net (code "32") (name "MOTOR2") (class "Default")
      (node (ref "ESC_INPUT") (pin "11") (pinfunction "11_11") (pintype "passive"))
      (node (ref "STM32F103_1") (pin "42") (pinfunction "PB6_42") (pintype "bidirectional"))
    )
    (net (code "33") (name "MOTOR3") (class "Default")
      (node (ref "ESC_INPUT") (pin "6") (pinfunction "6_6") (pintype "passive"))
      (node (ref "STM32F103_1") (pin "43") (pinfunction "PB7_43") (pintype "bidirectional"))
    )
    (net (code "34") (name "MOTOR4") (class "Default")
      (node (ref "ESC_INPUT") (pin "12") (pinfunction "12_12") (pintype "passive"))
      (node (ref "STM32F103_1") (pin "45") (pinfunction "PB8_45") (pintype "bidirectional"))
    )
    (net (code "35") (name "NRST") (class "Default")
      (node (ref "C20") (pin "2") (pinfunction "2_2") (pintype "passive"))
      (node (ref "R7") (pin "1") (pinfunction "1_1") (pintype "passive"))
      (node (ref "RST_BUTTON") (pin "4") (pinfunction "4_4") (pintype "passive"))
      (node (ref "U$1") (pin "NRST") (pinfunction "NRST_NRST") (pintype "bidirectional"))
    )
    (net (code "36") (name "NRST_103_0") (class "Default")
      (node (ref "C39") (pin "2") (pinfunction "2_2") (pintype "passive"))
      (node (ref "R27") (pin "1") (pinfunction "1_1") (pintype "passive"))
      (node (ref "RST_BUTTON2") (pin "4") (pinfunction "4_4") (pintype "passive"))
      (node (ref "STM32F103_0") (pin "7") (pinfunction "NRST_7") (pintype "bidirectional"))
    )
    (net (code "37") (name "NRST_103_1") (class "Default")
      (node (ref "C38") (pin "2") (pinfunction "2_2") (pintype "passive"))
      (node (ref "R26") (pin "1") (pinfunction "1_1") (pintype "passive"))
      (node (ref "RST_BUTTON1") (pin "4") (pinfunction "4_4") (pintype "passive"))
      (node (ref "STM32F103_1") (pin "7") (pinfunction "NRST_7") (pintype "bidirectional"))
    )
    (net (code "38") (name "Net-(32.7K-PIN1)") (class "Default")
      (node (ref "32.7K") (pin "1") (pinfunction "PIN1_1") (pintype "bidirectional"))
      (node (ref "C28") (pin "2") (pinfunction "2_2") (pintype "passive"))
      (node (ref "U$1") (pin "PC14") (pinfunction "PC14_PC14") (pintype "bidirectional"))
    )
    (net (code "39") (name "Net-(32.7K-PIN2)") (class "Default")
      (node (ref "32.7K") (pin "2") (pinfunction "PIN2_2") (pintype "bidirectional"))
      (node (ref "C29") (pin "2") (pinfunction "2_2") (pintype "passive"))
      (node (ref "U$1") (pin "PC15") (pinfunction "PC15_PC15") (pintype "bidirectional"))
    )
    (net (code "40") (name "Net-(32.7K1-PIN1)") (class "Default")
      (node (ref "32.7K1") (pin "1") (pinfunction "PIN1_1") (pintype "bidirectional"))
      (node (ref "C14") (pin "2") (pinfunction "2_2") (pintype "passive"))
      (node (ref "STM32F103_0") (pin "4") (pinfunction "OSC32_OUT_4") (pintype "bidirectional"))
    )
    (net (code "41") (name "Net-(32.7K1-PIN2)") (class "Default")
      (node (ref "32.7K1") (pin "2") (pinfunction "PIN2_2") (pintype "bidirectional"))
      (node (ref "C15") (pin "2") (pinfunction "2_2") (pintype "passive"))
      (node (ref "STM32F103_0") (pin "3") (pinfunction "OSC32_IN_3") (pintype "bidirectional"))
    )
    (net (code "42") (name "Net-(32.7K2-PIN1)") (class "Default")
      (node (ref "32.7K2") (pin "1") (pinfunction "PIN1_1") (pintype "bidirectional"))
      (node (ref "C32") (pin "2") (pinfunction "2_2") (pintype "passive"))
      (node (ref "STM32F103_1") (pin "4") (pinfunction "OSC32_OUT_4") (pintype "bidirectional"))
    )
    (net (code "43") (name "Net-(32.7K2-PIN2)") (class "Default")
      (node (ref "32.7K2") (pin "2") (pinfunction "PIN2_2") (pintype "bidirectional"))
      (node (ref "C33") (pin "2") (pinfunction "2_2") (pintype "passive"))
      (node (ref "STM32F103_1") (pin "3") (pinfunction "OSC32_IN_3") (pintype "bidirectional"))
    )
    (net (code "44") (name "Net-(C26-Pad2)") (class "Default")
      (node (ref "C26") (pin "2") (pinfunction "2_2") (pintype "passive"))
      (node (ref "R6") (pin "2") (pinfunction "2_2") (pintype "passive"))
      (node (ref "U$1") (pin "PH0") (pinfunction "PH0_PH0") (pintype "bidirectional"))
      (node (ref "Y2") (pin "2") (pinfunction "2_2") (pintype "passive"))
    )
    (net (code "45") (name "Net-(C27-Pad2)") (class "Default")
      (node (ref "C27") (pin "2") (pinfunction "2_2") (pintype "passive"))
      (node (ref "R6") (pin "1") (pinfunction "1_1") (pintype "passive"))
      (node (ref "U$1") (pin "PH1") (pinfunction "PH1_PH1") (pintype "bidirectional"))
      (node (ref "Y2") (pin "1") (pinfunction "1_1") (pintype "passive"))
    )
    (net (code "46") (name "Net-(LED1-PadA)") (class "Default")
      (node (ref "LED1") (pin "A") (pinfunction "A_A") (pintype "passive"))
      (node (ref "R8") (pin "1") (pinfunction "1_1") (pintype "passive"))
    )
    (net (code "47") (name "Net-(MPU6050-CPOUT)") (class "Default")
      (node (ref "C4") (pin "1") (pinfunction "1_1") (pintype "passive"))
      (node (ref "MPU6050") (pin "20") (pinfunction "CPOUT_20") (pintype "bidirectional"))
    )
    (net (code "48") (name "Net-(R4-Pad1)") (class "Default")
      (node (ref "R4") (pin "1") (pinfunction "1_1") (pintype "passive"))
      (node (ref "U$1") (pin "PB2") (pinfunction "PB2_PB2") (pintype "bidirectional"))
    )
    (net (code "49") (name "Net-(R5-Pad1)") (class "Default")
      (node (ref "R5") (pin "1") (pinfunction "1_1") (pintype "passive"))
      (node (ref "U$1") (pin "BOOT0") (pinfunction "BOOT0_BOOT0") (pintype "bidirectional"))
    )
    (net (code "50") (name "Net-(STM32F103_0-BOOT0)") (class "Default")
      (node (ref "R11") (pin "1") (pinfunction "1_1") (pintype "passive"))
      (node (ref "STM32F103_0") (pin "44") (pinfunction "BOOT0_44") (pintype "bidirectional"))
    )
    (net (code "51") (name "Net-(STM32F103_0-OSC_IN)") (class "Default")
      (node (ref "C12") (pin "2") (pinfunction "2_2") (pintype "passive"))
      (node (ref "R12") (pin "2") (pinfunction "2_2") (pintype "passive"))
      (node (ref "STM32F103_0") (pin "5") (pinfunction "OSC_IN_5") (pintype "bidirectional"))
      (node (ref "Y1") (pin "2") (pinfunction "2_2") (pintype "passive"))
    )
    (net (code "52") (name "Net-(STM32F103_0-OSC_OUT)") (class "Default")
      (node (ref "C13") (pin "2") (pinfunction "2_2") (pintype "passive"))
      (node (ref "R12") (pin "1") (pinfunction "1_1") (pintype "passive"))
      (node (ref "STM32F103_0") (pin "6") (pinfunction "OSC_OUT_6") (pintype "bidirectional"))
      (node (ref "Y1") (pin "1") (pinfunction "1_1") (pintype "passive"))
    )
    (net (code "53") (name "Net-(STM32F103_0-PB2)") (class "Default")
      (node (ref "R3") (pin "1") (pinfunction "1_1") (pintype "passive"))
      (node (ref "STM32F103_0") (pin "20") (pinfunction "PB2_20") (pintype "bidirectional"))
    )
    (net (code "54") (name "Net-(STM32F103_1-BOOT0)") (class "Default")
      (node (ref "R14") (pin "1") (pinfunction "1_1") (pintype "passive"))
      (node (ref "STM32F103_1") (pin "44") (pinfunction "BOOT0_44") (pintype "bidirectional"))
    )
    (net (code "55") (name "Net-(STM32F103_1-OSC_IN)") (class "Default")
      (node (ref "C30") (pin "2") (pinfunction "2_2") (pintype "passive"))
      (node (ref "R15") (pin "2") (pinfunction "2_2") (pintype "passive"))
      (node (ref "STM32F103_1") (pin "5") (pinfunction "OSC_IN_5") (pintype "bidirectional"))
      (node (ref "Y3") (pin "2") (pinfunction "2_2") (pintype "passive"))
    )
    (net (code "56") (name "Net-(STM32F103_1-OSC_OUT)") (class "Default")
      (node (ref "C31") (pin "2") (pinfunction "2_2") (pintype "passive"))
      (node (ref "R15") (pin "1") (pinfunction "1_1") (pintype "passive"))
      (node (ref "STM32F103_1") (pin "6") (pinfunction "OSC_OUT_6") (pintype "bidirectional"))
      (node (ref "Y3") (pin "1") (pinfunction "1_1") (pintype "passive"))
    )
    (net (code "57") (name "Net-(STM32F103_1-PB2)") (class "Default")
      (node (ref "R13") (pin "1") (pinfunction "1_1") (pintype "passive"))
      (node (ref "STM32F103_1") (pin "20") (pinfunction "PB2_20") (pintype "bidirectional"))
    )
    (net (code "58") (name "Net-(U$1-VCAP_1)") (class "Default")
      (node (ref "C23") (pin "1") (pinfunction "1_1") (pintype "passive"))
      (node (ref "U$1") (pin "VCAP1") (pinfunction "VCAP_1_VCAP1") (pintype "bidirectional"))
    )
    (net (code "59") (name "Net-(U$1-VCAP_2)") (class "Default")
      (node (ref "C24") (pin "1") (pinfunction "1_1") (pintype "passive"))
      (node (ref "U$1") (pin "VCAP2") (pinfunction "VCAP_2_VCAP2") (pintype "bidirectional"))
    )
    (net (code "60") (name "PA2") (class "Default")
      (node (ref "STM32F103_1") (pin "31") (pinfunction "PA10_31") (pintype "bidirectional"))
      (node (ref "U$1") (pin "PA2") (pinfunction "PA2_PA2") (pintype "bidirectional"))
    )
    (net (code "61") (name "PA3") (class "Default")
      (node (ref "STM32F103_1") (pin "30") (pinfunction "PA9_30") (pintype "bidirectional"))
      (node (ref "U$1") (pin "PA3") (pinfunction "PA3_PA3") (pintype "bidirectional"))
    )
    (net (code "62") (name "PA9") (class "Default")
      (node (ref "ISP_COM") (pin "4") (pinfunction "4_4") (pintype "passive"))
      (node (ref "STM32F103_0") (pin "31") (pinfunction "PA10_31") (pintype "bidirectional"))
      (node (ref "U$1") (pin "PA9") (pinfunction "PA9_PA9") (pintype "bidirectional"))
    )
    (net (code "63") (name "PA10") (class "Default")
      (node (ref "ISP_COM") (pin "3") (pinfunction "3_3") (pintype "passive"))
      (node (ref "STM32F103_0") (pin "30") (pinfunction "PA9_30") (pintype "bidirectional"))
      (node (ref "U$1") (pin "PA10") (pinfunction "PA10_PA10") (pintype "bidirectional"))
    )
    (net (code "64") (name "PB6") (class "Default")
      (node (ref "MPU6050") (pin "23") (pinfunction "SCL_23") (pintype "bidirectional"))
      (node (ref "MPU_DEBUG") (pin "3") (pinfunction "3_3") (pintype "passive"))
      (node (ref "R2") (pin "1") (pinfunction "1_1") (pintype "passive"))
      (node (ref "U$1") (pin "PB6") (pinfunction "PB6_PB6") (pintype "bidirectional"))
    )
    (net (code "65") (name "PB7") (class "Default")
      (node (ref "MPU6050") (pin "24") (pinfunction "SDA_24") (pintype "bidirectional"))
      (node (ref "MPU_DEBUG") (pin "4") (pinfunction "4_4") (pintype "passive"))
      (node (ref "R1") (pin "1") (pinfunction "1_1") (pintype "passive"))
      (node (ref "U$1") (pin "PB7") (pinfunction "PB7_PB7") (pintype "bidirectional"))
    )
    (net (code "66") (name "SCK") (class "Default")
      (node (ref "SPI_NRF2401") (pin "5") (pinfunction "5_5") (pintype "passive"))
      (node (ref "STM32F103_0") (pin "15") (pinfunction "PA5_15") (pintype "bidirectional"))
    )
    (net (code "67") (name "unconnected-(3V3_0-ADJ{slash}GND-Pad1)") (class "Default")
      (node (ref "3V3_0") (pin "1") (pinfunction "ADJ/GND_1") (pintype "passive"))
    )
    (net (code "68") (name "unconnected-(3V3_1-ADJ{slash}GND-Pad1)") (class "Default")
      (node (ref "3V3_1") (pin "1") (pinfunction "ADJ/GND_1") (pintype "passive"))
    )
    (net (code "69") (name "unconnected-(MPU6050-AD0{slash}SDO-Pad9)") (class "Default")
      (node (ref "MPU6050") (pin "9") (pinfunction "AD0/SDO_9") (pintype "bidirectional"))
    )
    (net (code "70") (name "unconnected-(MPU6050-AUX_CL-Pad7)") (class "Default")
      (node (ref "MPU6050") (pin "7") (pinfunction "AUX_CL_7") (pintype "bidirectional"))
    )
    (net (code "71") (name "unconnected-(MPU6050-AUX_DA-Pad6)") (class "Default")
      (node (ref "MPU6050") (pin "6") (pinfunction "AUX_DA_6") (pintype "bidirectional"))
    )
    (net (code "72") (name "unconnected-(MPU6050-INT-Pad12)") (class "Default")
      (node (ref "MPU6050") (pin "12") (pinfunction "INT_12") (pintype "bidirectional"))
    )
    (net (code "73") (name "unconnected-(MPU6050-NC0-Pad2)") (class "Default")
      (node (ref "MPU6050") (pin "2") (pinfunction "NC0_2") (pintype "bidirectional"))
    )
    (net (code "74") (name "unconnected-(MPU6050-NC1-Pad3)") (class "Default")
      (node (ref "MPU6050") (pin "3") (pinfunction "NC1_3") (pintype "bidirectional"))
    )
    (net (code "75") (name "unconnected-(MPU6050-NC2-Pad4)") (class "Default")
      (node (ref "MPU6050") (pin "4") (pinfunction "NC2_4") (pintype "bidirectional"))
    )
    (net (code "76") (name "unconnected-(MPU6050-NC3-Pad5)") (class "Default")
      (node (ref "MPU6050") (pin "5") (pinfunction "NC3_5") (pintype "bidirectional"))
    )
    (net (code "77") (name "unconnected-(MPU6050-NC4-Pad14)") (class "Default")
      (node (ref "MPU6050") (pin "14") (pinfunction "NC4_14") (pintype "bidirectional"))
    )
    (net (code "78") (name "unconnected-(MPU6050-NC5-Pad15)") (class "Default")
      (node (ref "MPU6050") (pin "15") (pinfunction "NC5_15") (pintype "bidirectional"))
    )
    (net (code "79") (name "unconnected-(MPU6050-NC6-Pad16)") (class "Default")
      (node (ref "MPU6050") (pin "16") (pinfunction "NC6_16") (pintype "bidirectional"))
    )
    (net (code "80") (name "unconnected-(MPU6050-NC7-Pad17)") (class "Default")
      (node (ref "MPU6050") (pin "17") (pinfunction "NC7_17") (pintype "bidirectional"))
    )
    (net (code "81") (name "unconnected-(MPU6050-RESV0-Pad19)") (class "Default")
      (node (ref "MPU6050") (pin "19") (pinfunction "RESV0_19") (pintype "bidirectional"))
    )
    (net (code "82") (name "unconnected-(MPU6050-RESV1-Pad21)") (class "Default")
      (node (ref "MPU6050") (pin "21") (pinfunction "RESV1_21") (pintype "bidirectional"))
    )
    (net (code "83") (name "unconnected-(MPU6050-RESV2-Pad22)") (class "Default")
      (node (ref "MPU6050") (pin "22") (pinfunction "RESV2_22") (pintype "bidirectional"))
    )
    (net (code "84") (name "unconnected-(RST_BUTTON-Pad2)") (class "Default")
      (node (ref "RST_BUTTON") (pin "2") (pinfunction "2_2") (pintype "passive"))
    )
    (net (code "85") (name "unconnected-(RST_BUTTON-Pad3)") (class "Default")
      (node (ref "RST_BUTTON") (pin "3") (pinfunction "3_3") (pintype "passive"))
    )
    (net (code "86") (name "unconnected-(RST_BUTTON1-Pad2)") (class "Default")
      (node (ref "RST_BUTTON1") (pin "2") (pinfunction "2_2") (pintype "passive"))
    )
    (net (code "87") (name "unconnected-(RST_BUTTON1-Pad3)") (class "Default")
      (node (ref "RST_BUTTON1") (pin "3") (pinfunction "3_3") (pintype "passive"))
    )
    (net (code "88") (name "unconnected-(RST_BUTTON2-Pad2)") (class "Default")
      (node (ref "RST_BUTTON2") (pin "2") (pinfunction "2_2") (pintype "passive"))
    )
    (net (code "89") (name "unconnected-(RST_BUTTON2-Pad3)") (class "Default")
      (node (ref "RST_BUTTON2") (pin "3") (pinfunction "3_3") (pintype "passive"))
    )
    (net (code "90") (name "unconnected-(STM32F103_0-PA0_WKUP-Pad10)") (class "Default")
      (node (ref "STM32F103_0") (pin "10") (pinfunction "PA0_WKUP_10") (pintype "bidirectional"))
    )
    (net (code "91") (name "unconnected-(STM32F103_0-PA1-Pad11)") (class "Default")
      (node (ref "STM32F103_0") (pin "11") (pinfunction "PA1_11") (pintype "bidirectional"))
    )
    (net (code "92") (name "unconnected-(STM32F103_0-PA2-Pad12)") (class "Default")
      (node (ref "STM32F103_0") (pin "12") (pinfunction "PA2_12") (pintype "bidirectional"))
    )
    (net (code "93") (name "unconnected-(STM32F103_0-PA8-Pad29)") (class "Default")
      (node (ref "STM32F103_0") (pin "29") (pinfunction "PA8_29") (pintype "bidirectional"))
    )
    (net (code "94") (name "unconnected-(STM32F103_0-PA11-Pad32)") (class "Default")
      (node (ref "STM32F103_0") (pin "32") (pinfunction "PA11_32") (pintype "bidirectional"))
    )
    (net (code "95") (name "unconnected-(STM32F103_0-PA12-Pad33)") (class "Default")
      (node (ref "STM32F103_0") (pin "33") (pinfunction "PA12_33") (pintype "bidirectional"))
    )
    (net (code "96") (name "unconnected-(STM32F103_0-PA15-Pad38)") (class "Default")
      (node (ref "STM32F103_0") (pin "38") (pinfunction "PA15_38") (pintype "bidirectional"))
    )
    (net (code "97") (name "unconnected-(STM32F103_0-PB0-Pad18)") (class "Default")
      (node (ref "STM32F103_0") (pin "18") (pinfunction "PB0_18") (pintype "bidirectional"))
    )
    (net (code "98") (name "unconnected-(STM32F103_0-PB1-Pad19)") (class "Default")
      (node (ref "STM32F103_0") (pin "19") (pinfunction "PB1_19") (pintype "bidirectional"))
    )
    (net (code "99") (name "unconnected-(STM32F103_0-PB3-Pad39)") (class "Default")
      (node (ref "STM32F103_0") (pin "39") (pinfunction "PB3_39") (pintype "bidirectional"))
    )
    (net (code "100") (name "unconnected-(STM32F103_0-PB4-Pad40)") (class "Default")
      (node (ref "STM32F103_0") (pin "40") (pinfunction "PB4_40") (pintype "bidirectional"))
    )
    (net (code "101") (name "unconnected-(STM32F103_0-PB5-Pad41)") (class "Default")
      (node (ref "STM32F103_0") (pin "41") (pinfunction "PB5_41") (pintype "bidirectional"))
    )
    (net (code "102") (name "unconnected-(STM32F103_0-PB6-Pad42)") (class "Default")
      (node (ref "STM32F103_0") (pin "42") (pinfunction "PB6_42") (pintype "bidirectional"))
    )
    (net (code "103") (name "unconnected-(STM32F103_0-PB7-Pad43)") (class "Default")
      (node (ref "STM32F103_0") (pin "43") (pinfunction "PB7_43") (pintype "bidirectional"))
    )
    (net (code "104") (name "unconnected-(STM32F103_0-PB8-Pad45)") (class "Default")
      (node (ref "STM32F103_0") (pin "45") (pinfunction "PB8_45") (pintype "bidirectional"))
    )
    (net (code "105") (name "unconnected-(STM32F103_0-PB9-Pad46)") (class "Default")
      (node (ref "STM32F103_0") (pin "46") (pinfunction "PB9_46") (pintype "bidirectional"))
    )
    (net (code "106") (name "unconnected-(STM32F103_0-PB10-Pad21)") (class "Default")
      (node (ref "STM32F103_0") (pin "21") (pinfunction "PB10_21") (pintype "bidirectional"))
    )
    (net (code "107") (name "unconnected-(STM32F103_0-PB11-Pad22)") (class "Default")
      (node (ref "STM32F103_0") (pin "22") (pinfunction "PB11_22") (pintype "bidirectional"))
    )
    (net (code "108") (name "unconnected-(STM32F103_0-PB12-Pad25)") (class "Default")
      (node (ref "STM32F103_0") (pin "25") (pinfunction "PB12_25") (pintype "bidirectional"))
    )
    (net (code "109") (name "unconnected-(STM32F103_0-PB13-Pad26)") (class "Default")
      (node (ref "STM32F103_0") (pin "26") (pinfunction "PB13_26") (pintype "bidirectional"))
    )
    (net (code "110") (name "unconnected-(STM32F103_0-PB14-Pad27)") (class "Default")
      (node (ref "STM32F103_0") (pin "27") (pinfunction "PB14_27") (pintype "bidirectional"))
    )
    (net (code "111") (name "unconnected-(STM32F103_0-PB15-Pad28)") (class "Default")
      (node (ref "STM32F103_0") (pin "28") (pinfunction "PB15_28") (pintype "bidirectional"))
    )
    (net (code "112") (name "unconnected-(STM32F103_0-PC13_TAMPER_RTC-Pad2)") (class "Default")
      (node (ref "STM32F103_0") (pin "2") (pinfunction "PC13_TAMPER_RTC_2") (pintype "bidirectional"))
    )
    (net (code "113") (name "unconnected-(STM32F103_0-VBAT-Pad1)") (class "Default")
      (node (ref "STM32F103_0") (pin "1") (pinfunction "VBAT_1") (pintype "bidirectional"))
    )
    (net (code "114") (name "unconnected-(STM32F103_1-PA0_WKUP-Pad10)") (class "Default")
      (node (ref "STM32F103_1") (pin "10") (pinfunction "PA0_WKUP_10") (pintype "bidirectional"))
    )
    (net (code "115") (name "unconnected-(STM32F103_1-PA1-Pad11)") (class "Default")
      (node (ref "STM32F103_1") (pin "11") (pinfunction "PA1_11") (pintype "bidirectional"))
    )
    (net (code "116") (name "unconnected-(STM32F103_1-PA2-Pad12)") (class "Default")
      (node (ref "STM32F103_1") (pin "12") (pinfunction "PA2_12") (pintype "bidirectional"))
    )
    (net (code "117") (name "unconnected-(STM32F103_1-PA3-Pad13)") (class "Default")
      (node (ref "STM32F103_1") (pin "13") (pinfunction "PA3_13") (pintype "bidirectional"))
    )
    (net (code "118") (name "unconnected-(STM32F103_1-PA4-Pad14)") (class "Default")
      (node (ref "STM32F103_1") (pin "14") (pinfunction "PA4_14") (pintype "bidirectional"))
    )
    (net (code "119") (name "unconnected-(STM32F103_1-PA5-Pad15)") (class "Default")
      (node (ref "STM32F103_1") (pin "15") (pinfunction "PA5_15") (pintype "bidirectional"))
    )
    (net (code "120") (name "unconnected-(STM32F103_1-PA6-Pad16)") (class "Default")
      (node (ref "STM32F103_1") (pin "16") (pinfunction "PA6_16") (pintype "bidirectional"))
    )
    (net (code "121") (name "unconnected-(STM32F103_1-PA7-Pad17)") (class "Default")
      (node (ref "STM32F103_1") (pin "17") (pinfunction "PA7_17") (pintype "bidirectional"))
    )
    (net (code "122") (name "unconnected-(STM32F103_1-PA8-Pad29)") (class "Default")
      (node (ref "STM32F103_1") (pin "29") (pinfunction "PA8_29") (pintype "bidirectional"))
    )
    (net (code "123") (name "unconnected-(STM32F103_1-PA11-Pad32)") (class "Default")
      (node (ref "STM32F103_1") (pin "32") (pinfunction "PA11_32") (pintype "bidirectional"))
    )
    (net (code "124") (name "unconnected-(STM32F103_1-PA12-Pad33)") (class "Default")
      (node (ref "STM32F103_1") (pin "33") (pinfunction "PA12_33") (pintype "bidirectional"))
    )
    (net (code "125") (name "unconnected-(STM32F103_1-PA15-Pad38)") (class "Default")
      (node (ref "STM32F103_1") (pin "38") (pinfunction "PA15_38") (pintype "bidirectional"))
    )
    (net (code "126") (name "unconnected-(STM32F103_1-PB0-Pad18)") (class "Default")
      (node (ref "STM32F103_1") (pin "18") (pinfunction "PB0_18") (pintype "bidirectional"))
    )
    (net (code "127") (name "unconnected-(STM32F103_1-PB1-Pad19)") (class "Default")
      (node (ref "STM32F103_1") (pin "19") (pinfunction "PB1_19") (pintype "bidirectional"))
    )
    (net (code "128") (name "unconnected-(STM32F103_1-PB3-Pad39)") (class "Default")
      (node (ref "STM32F103_1") (pin "39") (pinfunction "PB3_39") (pintype "bidirectional"))
    )
    (net (code "129") (name "unconnected-(STM32F103_1-PB4-Pad40)") (class "Default")
      (node (ref "STM32F103_1") (pin "40") (pinfunction "PB4_40") (pintype "bidirectional"))
    )
    (net (code "130") (name "unconnected-(STM32F103_1-PB9-Pad46)") (class "Default")
      (node (ref "STM32F103_1") (pin "46") (pinfunction "PB9_46") (pintype "bidirectional"))
    )
    (net (code "131") (name "unconnected-(STM32F103_1-PB10-Pad21)") (class "Default")
      (node (ref "STM32F103_1") (pin "21") (pinfunction "PB10_21") (pintype "bidirectional"))
    )
    (net (code "132") (name "unconnected-(STM32F103_1-PB11-Pad22)") (class "Default")
      (node (ref "STM32F103_1") (pin "22") (pinfunction "PB11_22") (pintype "bidirectional"))
    )
    (net (code "133") (name "unconnected-(STM32F103_1-PB12-Pad25)") (class "Default")
      (node (ref "STM32F103_1") (pin "25") (pinfunction "PB12_25") (pintype "bidirectional"))
    )
    (net (code "134") (name "unconnected-(STM32F103_1-PB13-Pad26)") (class "Default")
      (node (ref "STM32F103_1") (pin "26") (pinfunction "PB13_26") (pintype "bidirectional"))
    )
    (net (code "135") (name "unconnected-(STM32F103_1-PB14-Pad27)") (class "Default")
      (node (ref "STM32F103_1") (pin "27") (pinfunction "PB14_27") (pintype "bidirectional"))
    )
    (net (code "136") (name "unconnected-(STM32F103_1-PB15-Pad28)") (class "Default")
      (node (ref "STM32F103_1") (pin "28") (pinfunction "PB15_28") (pintype "bidirectional"))
    )
    (net (code "137") (name "unconnected-(STM32F103_1-PC13_TAMPER_RTC-Pad2)") (class "Default")
      (node (ref "STM32F103_1") (pin "2") (pinfunction "PC13_TAMPER_RTC_2") (pintype "bidirectional"))
    )
    (net (code "138") (name "unconnected-(STM32F103_1-VBAT-Pad1)") (class "Default")
      (node (ref "STM32F103_1") (pin "1") (pinfunction "VBAT_1") (pintype "bidirectional"))
    )
    (net (code "139") (name "unconnected-(U$1-PadPA0)") (class "Default")
      (node (ref "U$1") (pin "PA0") (pinfunction "PA0_PA0") (pintype "bidirectional"))
    )
    (net (code "140") (name "unconnected-(U$1-PadPA1)") (class "Default")
      (node (ref "U$1") (pin "PA1") (pinfunction "PA1_PA1") (pintype "bidirectional"))
    )
    (net (code "141") (name "unconnected-(U$1-PadPA4)") (class "Default")
      (node (ref "U$1") (pin "PA4") (pinfunction "PA4_PA4") (pintype "bidirectional"))
    )
    (net (code "142") (name "unconnected-(U$1-PadPA8)") (class "Default")
      (node (ref "U$1") (pin "PA8") (pinfunction "PA8_PA8") (pintype "bidirectional"))
    )
    (net (code "143") (name "unconnected-(U$1-PadPA11)") (class "Default")
      (node (ref "U$1") (pin "PA11") (pinfunction "PA11_PA11") (pintype "bidirectional"))
    )
    (net (code "144") (name "unconnected-(U$1-PadPA12)") (class "Default")
      (node (ref "U$1") (pin "PA12") (pinfunction "PA12_PA12") (pintype "bidirectional"))
    )
    (net (code "145") (name "unconnected-(U$1-PadPA15)") (class "Default")
      (node (ref "U$1") (pin "PA15") (pinfunction "PA15_PA15") (pintype "bidirectional"))
    )
    (net (code "146") (name "unconnected-(U$1-PadPB0)") (class "Default")
      (node (ref "U$1") (pin "PB0") (pinfunction "PB0_PB0") (pintype "bidirectional"))
    )
    (net (code "147") (name "unconnected-(U$1-PadPB1)") (class "Default")
      (node (ref "U$1") (pin "PB1") (pinfunction "PB1_PB1") (pintype "bidirectional"))
    )
    (net (code "148") (name "unconnected-(U$1-PadPB3)") (class "Default")
      (node (ref "U$1") (pin "PB3") (pinfunction "PB3_PB3") (pintype "bidirectional"))
    )
    (net (code "149") (name "unconnected-(U$1-PadPB4)") (class "Default")
      (node (ref "U$1") (pin "PB4") (pinfunction "PB4_PB4") (pintype "bidirectional"))
    )
    (net (code "150") (name "unconnected-(U$1-PadPB5)") (class "Default")
      (node (ref "U$1") (pin "PB5") (pinfunction "PB5_PB5") (pintype "bidirectional"))
    )
    (net (code "151") (name "unconnected-(U$1-PadPB8)") (class "Default")
      (node (ref "U$1") (pin "PB8") (pinfunction "PB8_PB8") (pintype "bidirectional"))
    )
    (net (code "152") (name "unconnected-(U$1-PadPB9)") (class "Default")
      (node (ref "U$1") (pin "PB9") (pinfunction "PB9_PB9") (pintype "bidirectional"))
    )
    (net (code "153") (name "unconnected-(U$1-PadPB11)") (class "Default")
      (node (ref "U$1") (pin "PB11") (pinfunction "PB11_PB11") (pintype "bidirectional"))
    )
    (net (code "154") (name "unconnected-(U$1-PadPB12)") (class "Default")
      (node (ref "U$1") (pin "PB12") (pinfunction "PB12_PB12") (pintype "bidirectional"))
    )
    (net (code "155") (name "unconnected-(U$1-PadPB13)") (class "Default")
      (node (ref "U$1") (pin "PB13") (pinfunction "PB13_PB13") (pintype "bidirectional"))
    )
    (net (code "156") (name "unconnected-(U$1-PadPB14)") (class "Default")
      (node (ref "U$1") (pin "PB14") (pinfunction "PB14_PB14") (pintype "bidirectional"))
    )
    (net (code "157") (name "unconnected-(U$1-PadPB15)") (class "Default")
      (node (ref "U$1") (pin "PB15") (pinfunction "PB15_PB15") (pintype "bidirectional"))
    )
    (net (code "158") (name "unconnected-(U$1-PadPC0)") (class "Default")
      (node (ref "U$1") (pin "PC0") (pinfunction "PC0_PC0") (pintype "bidirectional"))
    )
    (net (code "159") (name "unconnected-(U$1-PadPC1)") (class "Default")
      (node (ref "U$1") (pin "PC1") (pinfunction "PC1_PC1") (pintype "bidirectional"))
    )
    (net (code "160") (name "unconnected-(U$1-PadPC6)") (class "Default")
      (node (ref "U$1") (pin "PC6") (pinfunction "PC6_PC6") (pintype "bidirectional"))
    )
    (net (code "161") (name "unconnected-(U$1-PadPC7)") (class "Default")
      (node (ref "U$1") (pin "PC7") (pinfunction "PC7_PC7") (pintype "bidirectional"))
    )
    (net (code "162") (name "unconnected-(U$1-PadPC13)") (class "Default")
      (node (ref "U$1") (pin "PC13") (pinfunction "PC13_PC13") (pintype "bidirectional"))
    )
    (net (code "163") (name "unconnected-(U$1-PadPD0)") (class "Default")
      (node (ref "U$1") (pin "PD0") (pinfunction "PD0_PD0") (pintype "bidirectional"))
    )
    (net (code "164") (name "unconnected-(U$1-PadPD1)") (class "Default")
      (node (ref "U$1") (pin "PD1") (pinfunction "PD1_PD1") (pintype "bidirectional"))
    )
    (net (code "165") (name "unconnected-(U$1-PadPD3)") (class "Default")
      (node (ref "U$1") (pin "PD3") (pinfunction "PD3_PD3") (pintype "bidirectional"))
    )
    (net (code "166") (name "unconnected-(U$1-PadPD4)") (class "Default")
      (node (ref "U$1") (pin "PD4") (pinfunction "PD4_PD4") (pintype "bidirectional"))
    )
    (net (code "167") (name "unconnected-(U$1-PadPD5)") (class "Default")
      (node (ref "U$1") (pin "PD5") (pinfunction "PD5_PD5") (pintype "bidirectional"))
    )
    (net (code "168") (name "unconnected-(U$1-PadPD6)") (class "Default")
      (node (ref "U$1") (pin "PD6") (pinfunction "PD6_PD6") (pintype "bidirectional"))
    )
    (net (code "169") (name "unconnected-(U$1-PadPD7)") (class "Default")
      (node (ref "U$1") (pin "PD7") (pinfunction "PD7_PD7") (pintype "bidirectional"))
    )
    (net (code "170") (name "unconnected-(U$1-PadPD8)") (class "Default")
      (node (ref "U$1") (pin "PD8") (pinfunction "PD8_PD8") (pintype "bidirectional"))
    )
    (net (code "171") (name "unconnected-(U$1-PadPD9)") (class "Default")
      (node (ref "U$1") (pin "PD9") (pinfunction "PD9_PD9") (pintype "bidirectional"))
    )
    (net (code "172") (name "unconnected-(U$1-PadPD10)") (class "Default")
      (node (ref "U$1") (pin "PD10") (pinfunction "PD10_PD10") (pintype "bidirectional"))
    )
    (net (code "173") (name "unconnected-(U$1-PadPD11)") (class "Default")
      (node (ref "U$1") (pin "PD11") (pinfunction "PD11_PD11") (pintype "bidirectional"))
    )
    (net (code "174") (name "unconnected-(U$1-PadPD12)") (class "Default")
      (node (ref "U$1") (pin "PD12") (pinfunction "PD12_PD12") (pintype "bidirectional"))
    )
    (net (code "175") (name "unconnected-(U$1-PadPD13)") (class "Default")
      (node (ref "U$1") (pin "PD13") (pinfunction "PD13_PD13") (pintype "bidirectional"))
    )
    (net (code "176") (name "unconnected-(U$1-PadPD14)") (class "Default")
      (node (ref "U$1") (pin "PD14") (pinfunction "PD14_PD14") (pintype "bidirectional"))
    )
    (net (code "177") (name "unconnected-(U$1-PadPD15)") (class "Default")
      (node (ref "U$1") (pin "PD15") (pinfunction "PD15_PD15") (pintype "bidirectional"))
    )
    (net (code "178") (name "unconnected-(U$1-PadPE0)") (class "Default")
      (node (ref "U$1") (pin "PE0") (pinfunction "PE0_PE0") (pintype "bidirectional"))
    )
    (net (code "179") (name "unconnected-(U$1-PadPE1)") (class "Default")
      (node (ref "U$1") (pin "PE1") (pinfunction "PE1_PE1") (pintype "bidirectional"))
    )
    (net (code "180") (name "unconnected-(U$1-PadPE2)") (class "Default")
      (node (ref "U$1") (pin "PE2") (pinfunction "PE2_PE2") (pintype "bidirectional"))
    )
    (net (code "181") (name "unconnected-(U$1-PadPE3)") (class "Default")
      (node (ref "U$1") (pin "PE3") (pinfunction "PE3_PE3") (pintype "bidirectional"))
    )
    (net (code "182") (name "unconnected-(U$1-PadPE4)") (class "Default")
      (node (ref "U$1") (pin "PE4") (pinfunction "PE4_PE4") (pintype "bidirectional"))
    )
    (net (code "183") (name "unconnected-(U$1-PadPE5)") (class "Default")
      (node (ref "U$1") (pin "PE5") (pinfunction "PE5_PE5") (pintype "bidirectional"))
    )
    (net (code "184") (name "unconnected-(U$1-PadPE6)") (class "Default")
      (node (ref "U$1") (pin "PE6") (pinfunction "PE6_PE6") (pintype "bidirectional"))
    )
    (net (code "185") (name "unconnected-(U$1-PadPE9)") (class "Default")
      (node (ref "U$1") (pin "PE9") (pinfunction "PE9_PE9") (pintype "bidirectional"))
    )
    (net (code "186") (name "unconnected-(U$1-PadPE10)") (class "Default")
      (node (ref "U$1") (pin "PE10") (pinfunction "PE10_PE10") (pintype "bidirectional"))
    )
    (net (code "187") (name "unconnected-(U$1-PadPE11)") (class "Default")
      (node (ref "U$1") (pin "PE11") (pinfunction "PE11_PE11") (pintype "bidirectional"))
    )
    (net (code "188") (name "unconnected-(U$1-PadPE12)") (class "Default")
      (node (ref "U$1") (pin "PE12") (pinfunction "PE12_PE12") (pintype "bidirectional"))
    )
    (net (code "189") (name "unconnected-(U$1-PadPE13)") (class "Default")
      (node (ref "U$1") (pin "PE13") (pinfunction "PE13_PE13") (pintype "bidirectional"))
    )
    (net (code "190") (name "unconnected-(U$1-PadPE14)") (class "Default")
      (node (ref "U$1") (pin "PE14") (pinfunction "PE14_PE14") (pintype "bidirectional"))
    )
    (net (code "191") (name "unconnected-(U$1-PadPE15)") (class "Default")
      (node (ref "U$1") (pin "PE15") (pinfunction "PE15_PE15") (pintype "bidirectional"))
    )
    (net (code "192") (name "unconnected-(U$1-PadVBAT)") (class "Default")
      (node (ref "U$1") (pin "VBAT") (pinfunction "VBAT_VBAT") (pintype "bidirectional"))
    )
  )
)
